# v1_1.net
KiCad netlist of a schematic drawn in Altium Designer
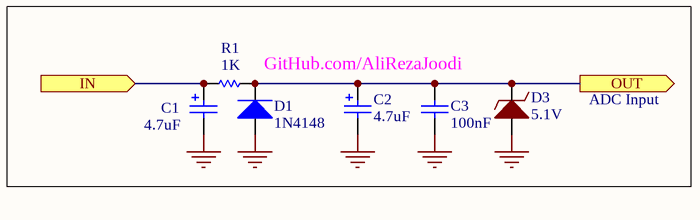
[diagram p0: v1.1.SchDoc]

(export (version "E")
  (design (tool "Eeschema 10.0.6"))
  (components
    (comp (ref "C1")
      (value "4.7uF")
      (footprint "CAPPR2.5-6.3x5")
      (description "Polarized Capacitor (Radial)")
      (fields (field (name "MANUFACTURER") "Generic Components") (field (name "PUBLISHER") "Altium Limited"))
      (libsource (lib "Miscellaneous Devices") (part "Cap Pol1"))
    )
    (comp (ref "C2")
      (value "4.7uF")
      (footprint "CAPPR2.5-6.3x5")
      (description "Polarized Capacitor (Radial)")
      (fields (field (name "MANUFACTURER") "Generic Components") (field (name "PUBLISHER") "Altium Limited"))
      (libsource (lib "Miscellaneous Devices") (part "Cap Pol1"))
    )
    (comp (ref "C3")
      (value "100nF")
      (footprint "CAPNTO2.54-3.05x1.78A")
      (description "Capacitor")
      (fields (field (name "MANUFACTURER") "Generic Components") (field (name "PUBLISHER") "Altium Limited"))
      (libsource (lib "Miscellaneous Devices") (part "Cap"))
    )
    (comp (ref "D1")
      (value "1N4148")
      (footprint "D_THD_AXIAL0.4_DO-41")
      (description "Diode,")
      (libsource (lib "Passive") (part "Diode"))
    )
    (comp (ref "D3")
      (value "5.1V")
      (footprint "D_THD_AXIAL0.3_DO-35")
      (description "Diode, Zener")
      (libsource (lib "Passive") (part "Diode_Zener"))
    )
    (comp (ref "R1")
      (value "1K")
      (footprint "R_THD_AXIAL0.4(1/4W)")
      (description "Resistor")
      (libsource (lib "Passive") (part "Resistor"))
    )
  )
  (nets
    (net (code "1") (name "/IN") (class "Default")
      (node (ref "C1") (pin "1") (pinfunction "1_1") (pintype "passive"))
      (node (ref "R1") (pin "1") (pinfunction "1_1") (pintype "passive"))
    )
    (net (code "2") (name "/OUT") (class "Default")
      (node (ref "C2") (pin "1") (pinfunction "1_1") (pintype "passive"))
      (node (ref "C3") (pin "2") (pinfunction "2_2") (pintype "passive"))
      (node (ref "D1") (pin "2") (pinfunction "K_2") (pintype "passive"))
      (node (ref "D3") (pin "2") (pinfunction "2_2") (pintype "passive"))
      (node (ref "R1") (pin "2") (pinfunction "2_2") (pintype "passive"))
    )
    (net (code "3") (name "GND") (class "Default")
      (node (ref "C1") (pin "2") (pinfunction "2_2") (pintype "passive"))
      (node (ref "C2") (pin "2") (pinfunction "2_2") (pintype "passive"))
      (node (ref "C3") (pin "1") (pinfunction "1_1") (pintype "passive"))
      (node (ref "D1") (pin "1") (pinfunction "A_1") (pintype "passive"))
      (node (ref "D3") (pin "1") (pinfunction "1_1") (pintype "passive"))
    )
  )
)
